# LCD1602.net
KiCad netlist of a schematic drawn in Altium Designer
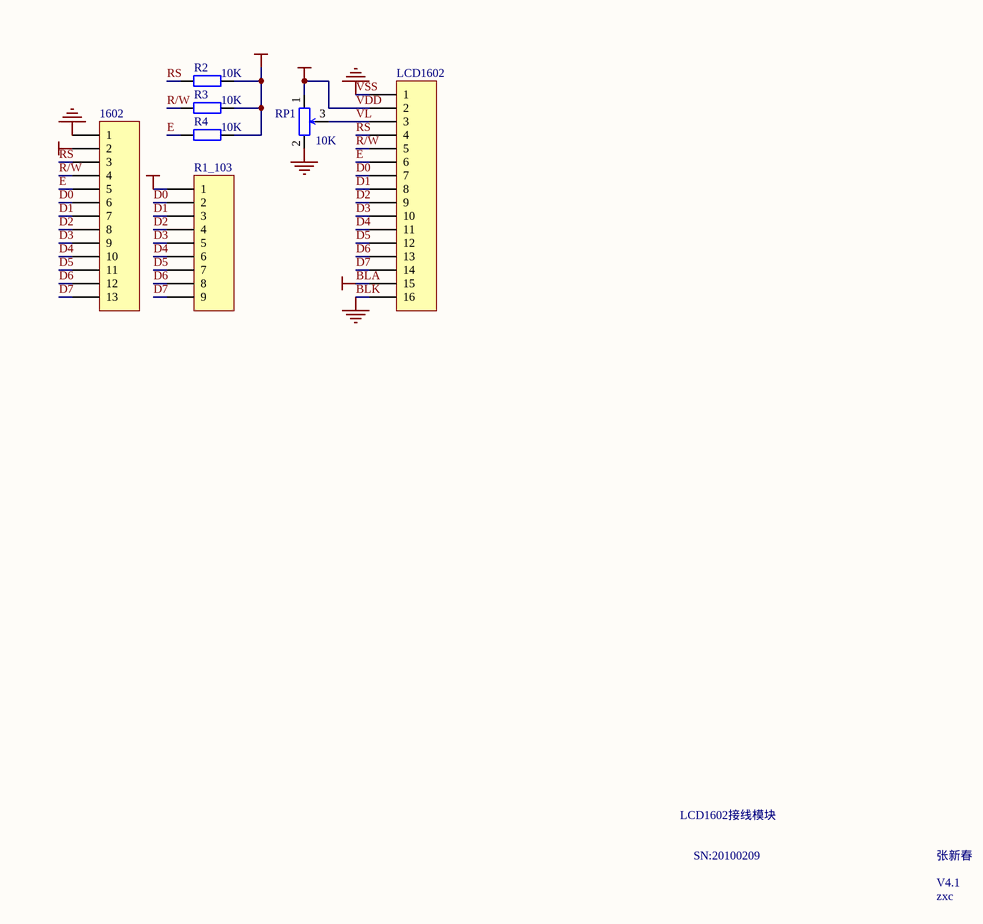
[diagram p0: LCD1602接线模块.SCHDOC]

(export (version "E")
  (design (tool "Eeschema 10.0.6"))
  (components
    (comp (ref "1602")
      (value "Header 13")
      (footprint "HDR1X13")
      (description "Header, 13-Pin")
      (fields (field (name "PUBLISHER") "Altium Limited"))
      (libsource (lib "Miscellaneous Connectors") (part "Header 13"))
    )
    (comp (ref "LCD1602")
      (value "Header 16")
      (footprint "HDR1X16")
      (description "Header, 16-Pin")
      (fields (field (name "PUBLISHER") "Altium Limited"))
      (libsource (lib "Miscellaneous Connectors") (part "Header 16"))
    )
    (comp (ref "R1_103")
      (value "Header 9")
      (footprint "HDR1X9")
      (description "Header, 9-Pin")
      (fields (field (name "PUBLISHER") "Altium Limited"))
      (libsource (lib "Miscellaneous Connectors") (part "Header 9"))
    )
    (comp (ref "R2")
      (value "10K")
      (footprint "TP-0805-R")
      (description "电阻")
      (fields (field (name "Comment") "Res") (field (name "PUBLISHER") "Altium Limited"))
      (libsource (lib "zxcourhc") (part "Res"))
    )
    (comp (ref "R3")
      (value "10K")
      (footprint "TP-0805-R")
      (description "电阻")
      (fields (field (name "Comment") "Res") (field (name "PUBLISHER") "Altium Limited"))
      (libsource (lib "zxcourhc") (part "Res"))
    )
    (comp (ref "R4")
      (value "10K")
      (footprint "TP-0805-R")
      (description "电阻")
      (fields (field (name "Comment") "Res") (field (name "PUBLISHER") "Altium Limited"))
      (libsource (lib "zxcourhc") (part "Res"))
    )
    (comp (ref "RP1")
      (value "10K")
      (footprint "SIP3-D")
      (description "j精调电阻")
      (fields (field (name "Comment") "Res _JT") (field (name "PUBLISHER") "Altium Limited"))
      (libsource (lib "zxcourhc") (part "Res _JT"))
    )
  )
  (nets
    (net (code "1") (name "/D0") (class "Default")
      (node (ref "1602") (pin "6") (pinfunction "6_6") (pintype "passive"))
      (node (ref "LCD1602") (pin "7") (pinfunction "7_7") (pintype "passive"))
      (node (ref "R1_103") (pin "2") (pinfunction "2_2") (pintype "passive"))
    )
    (net (code "2") (name "/D1") (class "Default")
      (node (ref "1602") (pin "7") (pinfunction "7_7") (pintype "passive"))
      (node (ref "LCD1602") (pin "8") (pinfunction "8_8") (pintype "passive"))
      (node (ref "R1_103") (pin "3") (pinfunction "3_3") (pintype "passive"))
    )
    (net (code "3") (name "/D2") (class "Default")
      (node (ref "1602") (pin "8") (pinfunction "8_8") (pintype "passive"))
      (node (ref "LCD1602") (pin "9") (pinfunction "9_9") (pintype "passive"))
      (node (ref "R1_103") (pin "4") (pinfunction "4_4") (pintype "passive"))
    )
    (net (code "4") (name "/D3") (class "Default")
      (node (ref "1602") (pin "9") (pinfunction "9_9") (pintype "passive"))
      (node (ref "LCD1602") (pin "10") (pinfunction "10_10") (pintype "passive"))
      (node (ref "R1_103") (pin "5") (pinfunction "5_5") (pintype "passive"))
    )
    (net (code "5") (name "/D4") (class "Default")
      (node (ref "1602") (pin "10") (pinfunction "10_10") (pintype "passive"))
      (node (ref "LCD1602") (pin "11") (pinfunction "11_11") (pintype "passive"))
      (node (ref "R1_103") (pin "6") (pinfunction "6_6") (pintype "passive"))
    )
    (net (code "6") (name "/D5") (class "Default")
      (node (ref "1602") (pin "11") (pinfunction "11_11") (pintype "passive"))
      (node (ref "LCD1602") (pin "12") (pinfunction "12_12") (pintype "passive"))
      (node (ref "R1_103") (pin "7") (pinfunction "7_7") (pintype "passive"))
    )
    (net (code "7") (name "/D6") (class "Default")
      (node (ref "1602") (pin "12") (pinfunction "12_12") (pintype "passive"))
      (node (ref "LCD1602") (pin "13") (pinfunction "13_13") (pintype "passive"))
      (node (ref "R1_103") (pin "8") (pinfunction "8_8") (pintype "passive"))
    )
    (net (code "8") (name "/D7") (class "Default")
      (node (ref "1602") (pin "13") (pinfunction "13_13") (pintype "passive"))
      (node (ref "LCD1602") (pin "14") (pinfunction "14_14") (pintype "passive"))
      (node (ref "R1_103") (pin "9") (pinfunction "9_9") (pintype "passive"))
    )
    (net (code "9") (name "/E") (class "Default")
      (node (ref "1602") (pin "5") (pinfunction "5_5") (pintype "passive"))
      (node (ref "LCD1602") (pin "6") (pinfunction "6_6") (pintype "passive"))
      (node (ref "R4") (pin "1") (pinfunction "1_1") (pintype "passive"))
    )
    (net (code "10") (name "/RS") (class "Default")
      (node (ref "1602") (pin "3") (pinfunction "3_3") (pintype "passive"))
      (node (ref "LCD1602") (pin "4") (pinfunction "4_4") (pintype "passive"))
      (node (ref "R2") (pin "1") (pinfunction "1_1") (pintype "passive"))
    )
    (net (code "11") (name "/R{slash}W") (class "Default")
      (node (ref "1602") (pin "4") (pinfunction "4_4") (pintype "passive"))
      (node (ref "LCD1602") (pin "5") (pinfunction "5_5") (pintype "passive"))
      (node (ref "R3") (pin "1") (pinfunction "1_1") (pintype "passive"))
    )
    (net (code "12") (name "/VL") (class "Default")
      (node (ref "LCD1602") (pin "3") (pinfunction "3_3") (pintype "passive"))
      (node (ref "RP1") (pin "3") (pinfunction "3_3") (pintype "passive"))
    )
    (net (code "13") (name "GND") (class "Default")
      (node (ref "1602") (pin "1") (pinfunction "1_1") (pintype "passive"))
      (node (ref "LCD1602") (pin "1") (pinfunction "1_1") (pintype "passive"))
      (node (ref "LCD1602") (pin "16") (pinfunction "16_16") (pintype "passive"))
      (node (ref "RP1") (pin "2") (pinfunction "2_2") (pintype "passive"))
    )
    (net (code "14") (name "VCC") (class "Default")
      (node (ref "1602") (pin "2") (pinfunction "2_2") (pintype "passive"))
      (node (ref "LCD1602") (pin "15") (pinfunction "15_15") (pintype "passive"))
      (node (ref "LCD1602") (pin "2") (pinfunction "2_2") (pintype "passive"))
      (node (ref "R1_103") (pin "1") (pinfunction "1_1") (pintype "passive"))
      (node (ref "R2") (pin "2") (pinfunction "2_2") (pintype "passive"))
      (node (ref "R3") (pin "2") (pinfunction "2_2") (pintype "passive"))
      (node (ref "R4") (pin "2") (pinfunction "2_2") (pintype "passive"))
      (node (ref "RP1") (pin "1") (pinfunction "1_1") (pintype "passive"))
    )
  )
)
